# PAGE1.net
KiCad netlist of a schematic drawn in Altium Designer
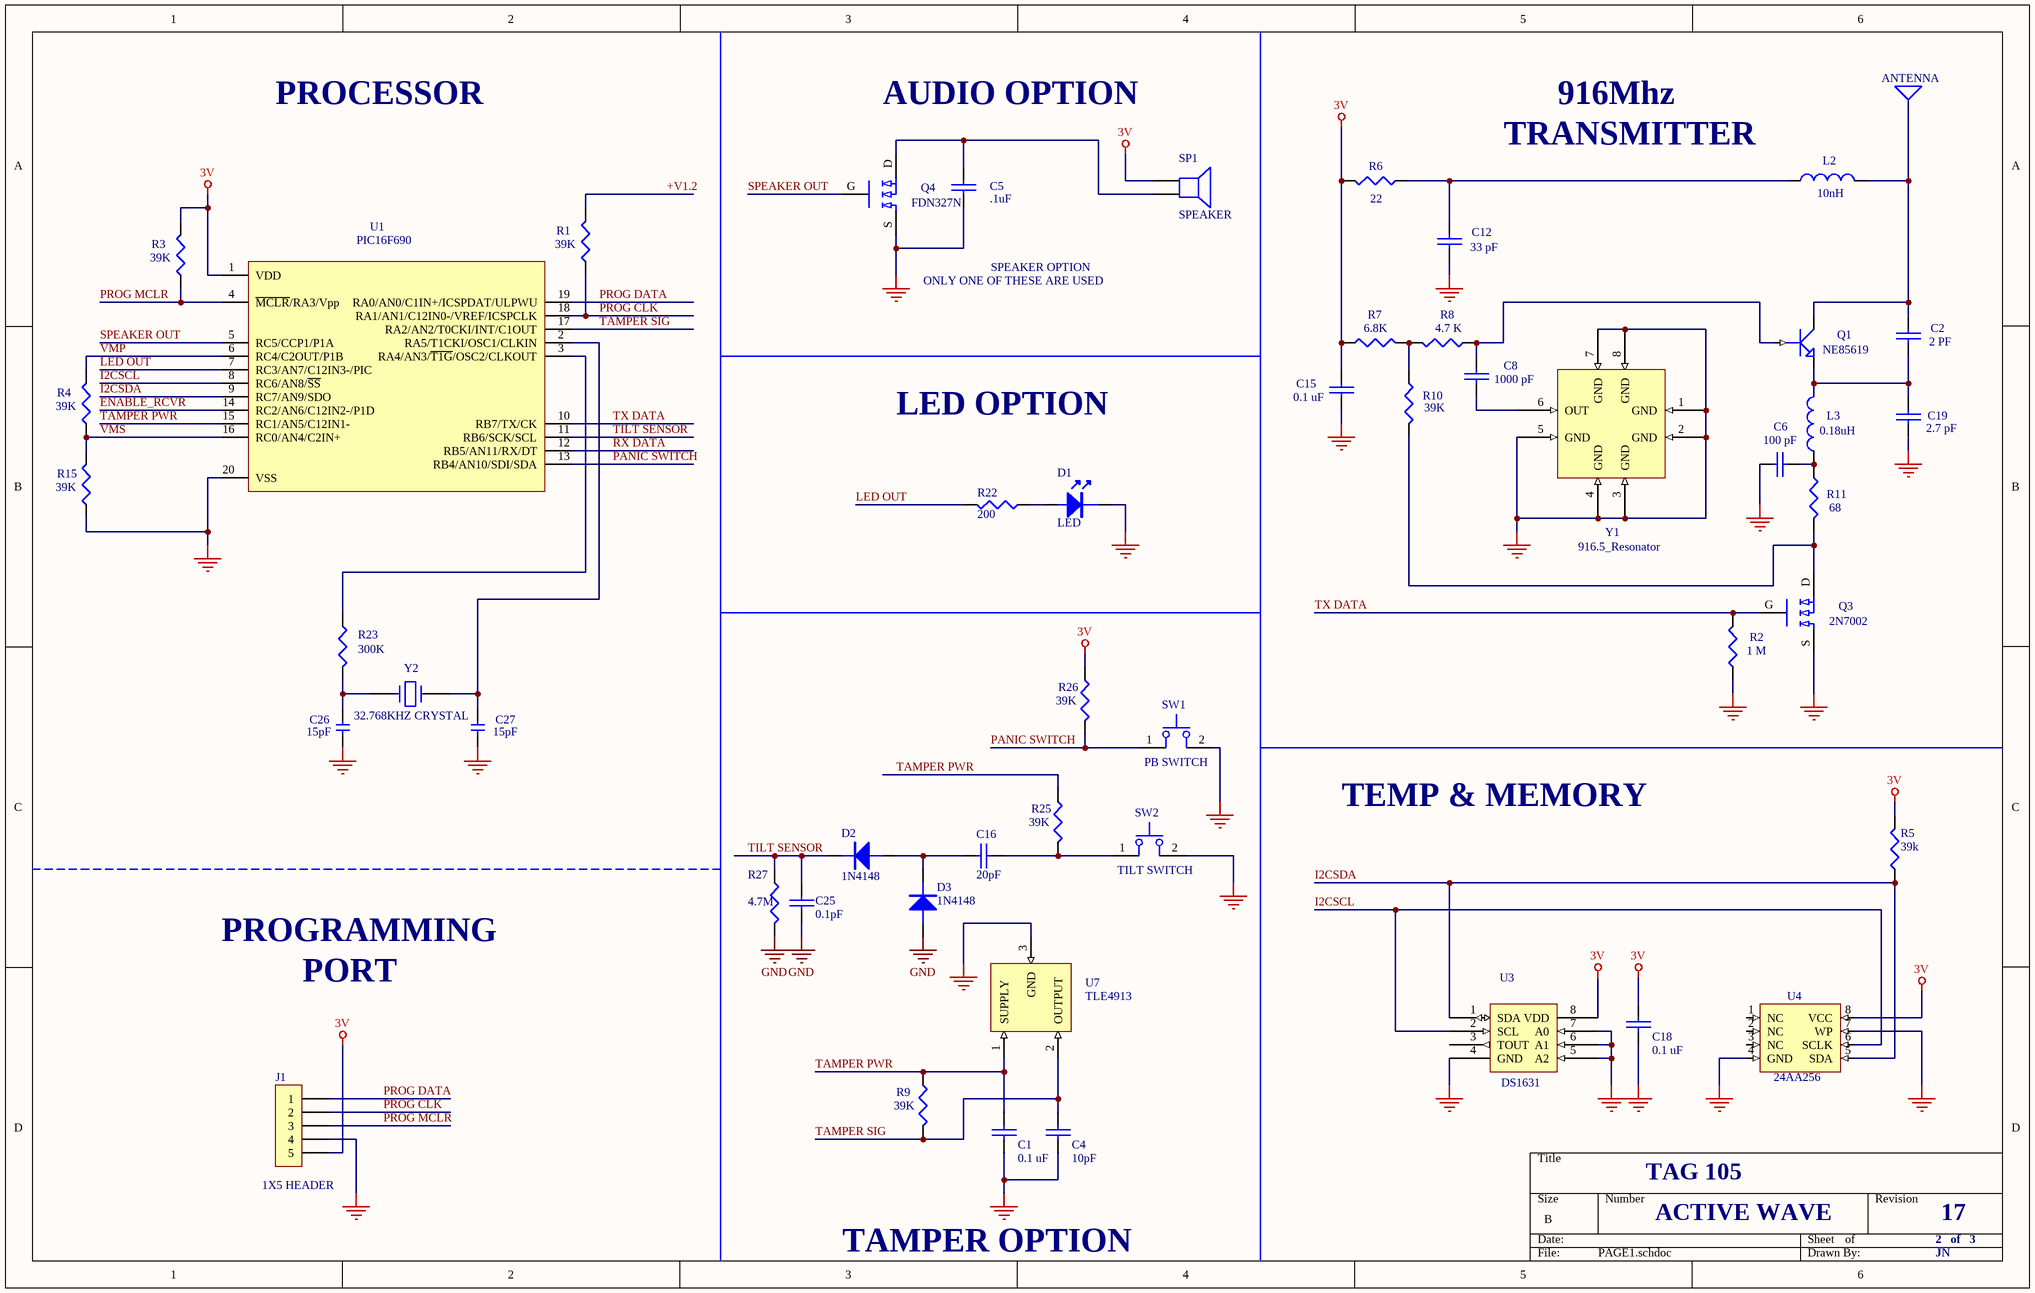
[diagram p0: PAGE1.schdoc]

(export (version "E")
  (design (tool "Eeschema 10.0.6"))
  (components
    (comp (ref "C1")
      (value "0.1 uF")
      (footprint "0603")
      (description "Capacitor")
      (libsource (lib "*") (part "CAP"))
    )
    (comp (ref "C2")
      (value "2 PF")
      (footprint "0603")
      (description "Capacitor")
      (libsource (lib "*") (part "CAP"))
    )
    (comp (ref "C4")
      (value "10pF")
      (footprint "0603")
      (description "Capacitor")
      (libsource (lib "*") (part "CAP"))
    )
    (comp (ref "C5")
      (value ".1uF")
      (footprint "0603")
      (description "Capacitor")
      (libsource (lib "*") (part "CAP"))
    )
    (comp (ref "C6")
      (value "100 pF")
      (footprint "0603")
      (description "Capacitor")
      (libsource (lib "*") (part "CAP"))
    )
    (comp (ref "C8")
      (value "1000 pF")
      (footprint "0603")
      (description "Capacitor")
      (libsource (lib "*") (part "CAP"))
    )
    (comp (ref "C12")
      (value "33 pF")
      (footprint "0603")
      (description "Capacitor")
      (libsource (lib "*") (part "CAP"))
    )
    (comp (ref "C15")
      (value "0.1 uF")
      (footprint "0603")
      (description "Capacitor")
      (libsource (lib "*") (part "CAP"))
    )
    (comp (ref "C16")
      (value "20pF")
      (footprint "0603")
      (description "Capacitor")
      (libsource (lib "*") (part "CAP"))
    )
    (comp (ref "C18")
      (value "0.1 uF")
      (footprint "0603")
      (description "Capacitor")
      (libsource (lib "*") (part "CAP"))
    )
    (comp (ref "C19")
      (value "2.7 pF")
      (footprint "0603")
      (description "Capacitor")
      (libsource (lib "*") (part "CAP"))
    )
    (comp (ref "C25")
      (value "0.1pF")
      (footprint "0603")
      (description "Capacitor")
      (libsource (lib "*") (part "CAP"))
    )
    (comp (ref "C26") (value "15pF") (footprint "0603") (libsource (lib "*") (part "C")))
    (comp (ref "C27") (value "15pF") (footprint "0603") (libsource (lib "*") (part "C")))
    (comp (ref "D1") (value "LED") (footprint "LED STANLEY H_1105W") (libsource (lib "*") (part "LED")))
    (comp (ref "D2")
      (value "1N4148")
      (footprint "sod123_021405")
      (description "Diode")
      (libsource (lib "*") (part "DIODE"))
    )
    (comp (ref "D3")
      (value "1N4148")
      (footprint "sod123_021405")
      (description "Diode")
      (libsource (lib "*") (part "DIODE"))
    )
    (comp (ref "J1")
      (value "1X5 HEADER")
      (footprint "1X5 HEADER")
      (description "Connector")
      (libsource (lib "*") (part "CON5"))
    )
    (comp (ref "L2") (value "10nH") (footprint "0603") (libsource (lib "*") (part "INDUCTOR")))
    (comp (ref "L3") (value "0.18uH") (footprint "0603") (libsource (lib "*") (part "INDUCTOR")))
    (comp (ref "Q1")
      (value "NE85619")
      (footprint "3 PIN ULTRA SUPER MINI MOLD")
      (description "NPN Transistor")
      (libsource (lib "*") (part "NPN1"))
    )
    (comp (ref "Q3") (value "2N7002") (libsource (lib "*") (part "FET 2")))
    (comp (ref "Q4") (value "FDN327N") (libsource (lib "*") (part "FET 2")))
    (comp (ref "R1") (value "39K") (footprint "0603") (libsource (lib "*") (part "RESISTOR")))
    (comp (ref "R2") (value "1 M") (footprint "0603") (libsource (lib "*") (part "RESISTOR")))
    (comp (ref "R3") (value "39K") (footprint "0603") (libsource (lib "*") (part "RESISTOR")))
    (comp (ref "R4") (value "39K") (footprint "0603") (libsource (lib "*") (part "RESISTOR")))
    (comp (ref "R5") (value "39k") (footprint "0603") (libsource (lib "*") (part "RESISTOR")))
    (comp (ref "R6") (value "22") (footprint "0603") (libsource (lib "*") (part "RESISTOR")))
    (comp (ref "R7") (value "6.8K") (footprint "0603") (libsource (lib "*") (part "RESISTOR")))
    (comp (ref "R8") (value "4.7 K") (footprint "0603") (libsource (lib "*") (part "RESISTOR")))
    (comp (ref "R9") (value "39K") (footprint "0603") (libsource (lib "*") (part "RESISTOR")))
    (comp (ref "R10") (value "39K") (footprint "0603") (libsource (lib "*") (part "RESISTOR")))
    (comp (ref "R11") (value "68") (footprint "0603") (libsource (lib "*") (part "RES1")))
    (comp (ref "R15") (value "39K") (footprint "0603") (libsource (lib "*") (part "RESISTOR")))
    (comp (ref "R22") (value "200") (footprint "0603") (libsource (lib "*") (part "RES1")))
    (comp (ref "R23") (value "300K") (footprint "0603") (libsource (lib "*") (part "RESISTOR")))
    (comp (ref "R25") (value "39K") (footprint "0603") (libsource (lib "*") (part "RESISTOR")))
    (comp (ref "R26") (value "39K") (footprint "0603") (libsource (lib "*") (part "RESISTOR")))
    (comp (ref "R27") (value "4.7M") (footprint "0603") (libsource (lib "*") (part "RESISTOR")))
    (comp (ref "SP1") (value "SPEAKER") (footprint "SMT_1028-S-R") (libsource (lib "*") (part "SPEAKER")))
    (comp (ref "SW1")
      (value "PB SWITCH")
      (footprint "SWITCH PB REVERSED_082907")
      (libsource (lib "Common") (part "SWITCH PB"))
    )
    (comp (ref "SW2")
      (value "TILT SWITCH")
      (footprint "SQ-SEN-200")
      (libsource (lib "Common") (part "SWITCH PB"))
    )
    (comp (ref "U1") (value "PIC16F690") (libsource (lib "*") (part "PIC16F690")))
    (comp (ref "U3") (value "DS1631") (footprint "SO8 SMALL") (libsource (lib "*") (part "DS1631")))
    (comp (ref "U4") (value "24AA256") (footprint "SO8") (libsource (lib "*") (part "24AA256")))
    (comp (ref "U7") (value "TLE4913") (footprint "SOT23W") (libsource (lib "*") (part "HALL EFFECT SWITCH")))
    (comp (ref "Y1")
      (value "916.5_Resonator")
      (footprint "RESONATOR")
      (libsource (lib "*") (part "RESONATOR"))
    )
    (comp (ref "Y2")
      (value "32.768KHZ CRYSTAL")
      (footprint "CRYSTAL ABRACON ABS07")
      (description "Crystal")
      (libsource (lib "*") (part "CRYSTAL"))
    )
  )
  (nets
    (net (code "1") (name "/+V1.2") (class "Default")
      (node (ref "R1") (pin "2") (pinfunction "2_2") (pintype "passive"))
    )
    (net (code "2") (name "/ENABLE_RCVR") (class "Default")
      (node (ref "U1") (pin "14") (pinfunction "RC2/AN6/C12IN2-/P1D_14") (pintype "passive"))
    )
    (net (code "3") (name "/I2CSCL") (class "Default")
      (node (ref "U1") (pin "8") (pinfunction "RC6/AN8/~{SS}_8") (pintype "passive"))
      (node (ref "U3") (pin "2") (pinfunction "SCL_2") (pintype "input"))
      (node (ref "U4") (pin "6") (pinfunction "SCLK_6") (pintype "input"))
    )
    (net (code "4") (name "/I2CSDA") (class "Default")
      (node (ref "R5") (pin "1") (pinfunction "1_1") (pintype "passive"))
      (node (ref "U1") (pin "9") (pinfunction "RC7/AN9/SDO_9") (pintype "passive"))
      (node (ref "U3") (pin "1") (pinfunction "SDA_1") (pintype "bidirectional"))
      (node (ref "U4") (pin "5") (pinfunction "SDA_5") (pintype "input"))
    )
    (net (code "5") (name "/LED OUT") (class "Default")
      (node (ref "R22") (pin "2") (pinfunction "2_2") (pintype "passive"))
      (node (ref "U1") (pin "7") (pinfunction "RC3/AN7/C12IN3-/PIC_7") (pintype "passive"))
    )
    (net (code "6") (name "/PANIC SWITCH") (class "Default")
      (node (ref "R26") (pin "2") (pinfunction "2_2") (pintype "passive"))
      (node (ref "SW1") (pin "1") (pinfunction "1_1") (pintype "passive"))
      (node (ref "U1") (pin "13") (pinfunction "RB4/AN10/SDI/SDA_13") (pintype "passive"))
    )
    (net (code "7") (name "/PROG CLK") (class "Default")
      (node (ref "J1") (pin "2") (pinfunction "2_2") (pintype "passive"))
      (node (ref "R1") (pin "1") (pinfunction "1_1") (pintype "passive"))
      (node (ref "U1") (pin "18") (pinfunction "RA1/AN1/C12IN0-/VREF/ICSPCLK_18") (pintype "passive"))
    )
    (net (code "8") (name "/PROG DATA") (class "Default")
      (node (ref "J1") (pin "1") (pinfunction "1_1") (pintype "passive"))
      (node (ref "U1") (pin "19") (pinfunction "RA0/AN0/C1IN+/ICSPDAT/ULPWU_19") (pintype "passive"))
    )
    (net (code "9") (name "/PROG MCLR") (class "Default")
      (node (ref "J1") (pin "3") (pinfunction "3_3") (pintype "passive"))
      (node (ref "R3") (pin "1") (pinfunction "1_1") (pintype "passive"))
      (node (ref "U1") (pin "4") (pinfunction "~{MCLR}/RA3/Vpp_4") (pintype "passive"))
    )
    (net (code "10") (name "/RX DATA") (class "Default")
      (node (ref "U1") (pin "12") (pinfunction "RB5/AN11/RX/DT_12") (pintype "passive"))
    )
    (net (code "11") (name "/SPEAKER OUT") (class "Default")
      (node (ref "Q4") (pin "G") (pinfunction "G_G") (pintype "passive"))
      (node (ref "U1") (pin "5") (pinfunction "RC5/CCP1/P1A_5") (pintype "passive"))
    )
    (net (code "12") (name "/TAMPER PWR") (class "Default")
      (node (ref "C1") (pin "1") (pinfunction "1_1") (pintype "passive"))
      (node (ref "R25") (pin "1") (pinfunction "1_1") (pintype "passive"))
      (node (ref "R9") (pin "1") (pinfunction "1_1") (pintype "passive"))
      (node (ref "U1") (pin "15") (pinfunction "RC1/AN5/C12IN1-_15") (pintype "passive"))
      (node (ref "U7") (pin "1") (pinfunction "SUPPLY_1") (pintype "input"))
    )
    (net (code "13") (name "/TAMPER SIG") (class "Default")
      (node (ref "C4") (pin "1") (pinfunction "1_1") (pintype "passive"))
      (node (ref "R9") (pin "2") (pinfunction "2_2") (pintype "passive"))
      (node (ref "U1") (pin "17") (pinfunction "RA2/AN2/T0CKI/INT/C1OUT_17") (pintype "passive"))
      (node (ref "U7") (pin "2") (pinfunction "OUTPUT_2") (pintype "input"))
    )
    (net (code "14") (name "/TILT SENSOR") (class "Default")
      (node (ref "C25") (pin "1") (pinfunction "1_1") (pintype "passive"))
      (node (ref "D2") (pin "K") (pinfunction "K_K") (pintype "passive"))
      (node (ref "R27") (pin "1") (pinfunction "1_1") (pintype "passive"))
      (node (ref "U1") (pin "11") (pinfunction "RB6/SCK/SCL_11") (pintype "passive"))
    )
    (net (code "15") (name "/TX DATA") (class "Default")
      (node (ref "Q3") (pin "G") (pinfunction "G_G") (pintype "passive"))
      (node (ref "R2") (pin "2") (pinfunction "2_2") (pintype "passive"))
      (node (ref "U1") (pin "10") (pinfunction "RB7/TX/CK_10") (pintype "passive"))
    )
    (net (code "16") (name "/VMP") (class "Default")
      (node (ref "R4") (pin "2") (pinfunction "2_2") (pintype "passive"))
      (node (ref "U1") (pin "6") (pinfunction "RC4/C2OUT/P1B_6") (pintype "passive"))
    )
    (net (code "17") (name "/VMS") (class "Default")
      (node (ref "R15") (pin "2") (pinfunction "2_2") (pintype "passive"))
      (node (ref "R4") (pin "1") (pinfunction "1_1") (pintype "passive"))
      (node (ref "U1") (pin "16") (pinfunction "RC0/AN4/C2IN+_16") (pintype "passive"))
    )
    (net (code "18") (name "3V") (class "Default")
      (node (ref "C15") (pin "1") (pinfunction "1_1") (pintype "passive"))
      (node (ref "C18") (pin "1") (pinfunction "1_1") (pintype "passive"))
      (node (ref "J1") (pin "5") (pinfunction "5_5") (pintype "passive"))
      (node (ref "R26") (pin "1") (pinfunction "1_1") (pintype "passive"))
      (node (ref "R3") (pin "2") (pinfunction "2_2") (pintype "passive"))
      (node (ref "R5") (pin "2") (pinfunction "2_2") (pintype "passive"))
      (node (ref "R6") (pin "2") (pinfunction "2_2") (pintype "passive"))
      (node (ref "R7") (pin "1") (pinfunction "1_1") (pintype "passive"))
      (node (ref "SP1") (pin "1") (pinfunction "1_1") (pintype "passive"))
      (node (ref "U1") (pin "1") (pinfunction "VDD_1") (pintype "passive"))
      (node (ref "U3") (pin "8") (pinfunction "VDD_8") (pintype "power_in"))
      (node (ref "U4") (pin "8") (pinfunction "VCC_8") (pintype "input"))
    )
    (net (code "19") (name "GND") (class "Default")
      (node (ref "C1") (pin "2") (pinfunction "2_2") (pintype "passive"))
      (node (ref "C12") (pin "2") (pinfunction "2_2") (pintype "passive"))
      (node (ref "C15") (pin "2") (pinfunction "2_2") (pintype "passive"))
      (node (ref "C18") (pin "2") (pinfunction "2_2") (pintype "passive"))
      (node (ref "C19") (pin "2") (pinfunction "2_2") (pintype "passive"))
      (node (ref "C25") (pin "2") (pinfunction "2_2") (pintype "passive"))
      (node (ref "C26") (pin "1") (pinfunction "1_1") (pintype "passive"))
      (node (ref "C27") (pin "1") (pinfunction "1_1") (pintype "passive"))
      (node (ref "C4") (pin "2") (pinfunction "2_2") (pintype "passive"))
      (node (ref "C5") (pin "2") (pinfunction "2_2") (pintype "passive"))
      (node (ref "C6") (pin "1") (pinfunction "1_1") (pintype "passive"))
      (node (ref "D1") (pin "K") (pinfunction "K_K") (pintype "passive"))
      (node (ref "D3") (pin "A") (pinfunction "A_A") (pintype "passive"))
      (node (ref "J1") (pin "4") (pinfunction "4_4") (pintype "passive"))
      (node (ref "Q3") (pin "S") (pinfunction "S_S") (pintype "passive"))
      (node (ref "Q4") (pin "S") (pinfunction "S_S") (pintype "passive"))
      (node (ref "R15") (pin "1") (pinfunction "1_1") (pintype "passive"))
      (node (ref "R2") (pin "1") (pinfunction "1_1") (pintype "passive"))
      (node (ref "R27") (pin "2") (pinfunction "2_2") (pintype "passive"))
      (node (ref "SW1") (pin "2") (pinfunction "2_2") (pintype "passive"))
      (node (ref "SW2") (pin "2") (pinfunction "2_2") (pintype "passive"))
      (node (ref "U1") (pin "20") (pinfunction "VSS_20") (pintype "passive"))
      (node (ref "U3") (pin "4") (pinfunction "GND_4") (pintype "power_in"))
      (node (ref "U3") (pin "5") (pinfunction "A2_5") (pintype "input"))
      (node (ref "U3") (pin "6") (pinfunction "A1_6") (pintype "input"))
      (node (ref "U3") (pin "7") (pinfunction "A0_7") (pintype "input"))
      (node (ref "U4") (pin "4") (pinfunction "GND_4") (pintype "input"))
      (node (ref "U4") (pin "7") (pinfunction "WP_7") (pintype "input"))
      (node (ref "U7") (pin "3") (pinfunction "GND_3") (pintype "input"))
      (node (ref "Y1") (pin "1") (pinfunction "GND_1") (pintype "input"))
      (node (ref "Y1") (pin "2") (pinfunction "GND_2") (pintype "input"))
      (node (ref "Y1") (pin "3") (pinfunction "GND_3") (pintype "input"))
      (node (ref "Y1") (pin "4") (pinfunction "GND_4") (pintype "input"))
      (node (ref "Y1") (pin "5") (pinfunction "GND_5") (pintype "input"))
      (node (ref "Y1") (pin "7") (pinfunction "GND_7") (pintype "input"))
      (node (ref "Y1") (pin "8") (pinfunction "GND_8") (pintype "input"))
    )
    (net (code "20") (name "Net-(C2-Pad1)") (class "Default")
      (node (ref "C2") (pin "1") (pinfunction "1_1") (pintype "passive"))
      (node (ref "L2") (pin "2") (pinfunction "2_2") (pintype "passive"))
      (node (ref "Q1") (pin "C") (pinfunction "C_C") (pintype "passive"))
    )
    (net (code "21") (name "Net-(C5-Pad1)") (class "Default")
      (node (ref "C5") (pin "1") (pinfunction "1_1") (pintype "passive"))
      (node (ref "Q4") (pin "D") (pinfunction "D_D") (pintype "passive"))
      (node (ref "SP1") (pin "2") (pinfunction "2_2") (pintype "passive"))
    )
    (net (code "22") (name "Net-(C6-Pad2)") (class "Default")
      (node (ref "C6") (pin "2") (pinfunction "2_2") (pintype "passive"))
      (node (ref "L3") (pin "1") (pinfunction "1_1") (pintype "passive"))
      (node (ref "R11") (pin "1") (pinfunction "1_1") (pintype "passive"))
    )
    (net (code "23") (name "Net-(C8-Pad1)") (class "Default")
      (node (ref "C8") (pin "1") (pinfunction "1_1") (pintype "passive"))
      (node (ref "Q1") (pin "B") (pinfunction "B_B") (pintype "input"))
      (node (ref "R8") (pin "1") (pinfunction "1_1") (pintype "passive"))
    )
    (net (code "24") (name "Net-(C12-Pad1)") (class "Default")
      (node (ref "C12") (pin "1") (pinfunction "1_1") (pintype "passive"))
      (node (ref "L2") (pin "1") (pinfunction "1_1") (pintype "passive"))
      (node (ref "R6") (pin "1") (pinfunction "1_1") (pintype "passive"))
    )
    (net (code "25") (name "Net-(C16-Pad1)") (class "Default")
      (node (ref "C16") (pin "1") (pinfunction "1_1") (pintype "passive"))
      (node (ref "D2") (pin "A") (pinfunction "A_A") (pintype "passive"))
      (node (ref "D3") (pin "K") (pinfunction "K_K") (pintype "passive"))
    )
    (net (code "26") (name "Net-(C16-Pad2)") (class "Default")
      (node (ref "C16") (pin "2") (pinfunction "2_2") (pintype "passive"))
      (node (ref "R25") (pin "2") (pinfunction "2_2") (pintype "passive"))
      (node (ref "SW2") (pin "1") (pinfunction "1_1") (pintype "passive"))
    )
    (net (code "27") (name "Net-(C19-Pad1)") (class "Default")
      (node (ref "C19") (pin "1") (pinfunction "1_1") (pintype "passive"))
      (node (ref "C2") (pin "2") (pinfunction "2_2") (pintype "passive"))
      (node (ref "L3") (pin "2") (pinfunction "2_2") (pintype "passive"))
      (node (ref "Q1") (pin "E") (pinfunction "E_E") (pintype "passive"))
    )
    (net (code "28") (name "Net-(C26-Pad2)") (class "Default")
      (node (ref "C26") (pin "2") (pinfunction "2_2") (pintype "passive"))
      (node (ref "R23") (pin "2") (pinfunction "2_2") (pintype "passive"))
      (node (ref "Y2") (pin "2") (pinfunction "2_2") (pintype "passive"))
    )
    (net (code "29") (name "Net-(D1-PadA)") (class "Default")
      (node (ref "D1") (pin "A") (pinfunction "A_A") (pintype "passive"))
      (node (ref "R22") (pin "1") (pinfunction "1_1") (pintype "passive"))
    )
    (net (code "30") (name "Net-(Q3-PadD)") (class "Default")
      (node (ref "Q3") (pin "D") (pinfunction "D_D") (pintype "passive"))
      (node (ref "R10") (pin "2") (pinfunction "2_2") (pintype "passive"))
      (node (ref "R11") (pin "2") (pinfunction "2_2") (pintype "passive"))
    )
    (net (code "31") (name "Net-(R10-Pad1)") (class "Default")
      (node (ref "R10") (pin "1") (pinfunction "1_1") (pintype "passive"))
      (node (ref "R7") (pin "2") (pinfunction "2_2") (pintype "passive"))
      (node (ref "R8") (pin "2") (pinfunction "2_2") (pintype "passive"))
    )
    (net (code "32") (name "Net-(U1-RA4{slash}AN3{slash}~{T1G}{slash}OSC2{slash}CLKOUT)") (class "Default")
      (node (ref "R23") (pin "1") (pinfunction "1_1") (pintype "passive"))
      (node (ref "U1") (pin "3") (pinfunction "RA4/AN3/~{T1G}/OSC2/CLKOUT_3") (pintype "passive"))
    )
    (net (code "33") (name "Net-(U1-RA5{slash}T1CKI{slash}OSC1{slash}CLKIN)") (class "Default")
      (node (ref "C27") (pin "2") (pinfunction "2_2") (pintype "passive"))
      (node (ref "U1") (pin "2") (pinfunction "RA5/T1CKI/OSC1/CLKIN_2") (pintype "passive"))
      (node (ref "Y2") (pin "1") (pinfunction "1_1") (pintype "passive"))
    )
    (net (code "34") (name "Net-(Y1-OUT)") (class "Default")
      (node (ref "C8") (pin "2") (pinfunction "2_2") (pintype "passive"))
      (node (ref "Y1") (pin "6") (pinfunction "OUT_6") (pintype "input"))
    )
    (net (code "35") (name "unconnected-(U3-TOUT-Pad3)") (class "Default")
      (node (ref "U3") (pin "3") (pinfunction "TOUT_3") (pintype "output"))
    )
    (net (code "36") (name "unconnected-(U4-NC-Pad1)") (class "Default")
      (node (ref "U4") (pin "1") (pinfunction "NC_1") (pintype "input"))
    )
    (net (code "37") (name "unconnected-(U4-NC-Pad2)") (class "Default")
      (node (ref "U4") (pin "2") (pinfunction "NC_2") (pintype "input"))
    )
    (net (code "38") (name "unconnected-(U4-NC-Pad3)") (class "Default")
      (node (ref "U4") (pin "3") (pinfunction "NC_3") (pintype "input"))
    )
  )
)
